# relay_interface.net
KiCad netlist of a schematic drawn in EAGLE
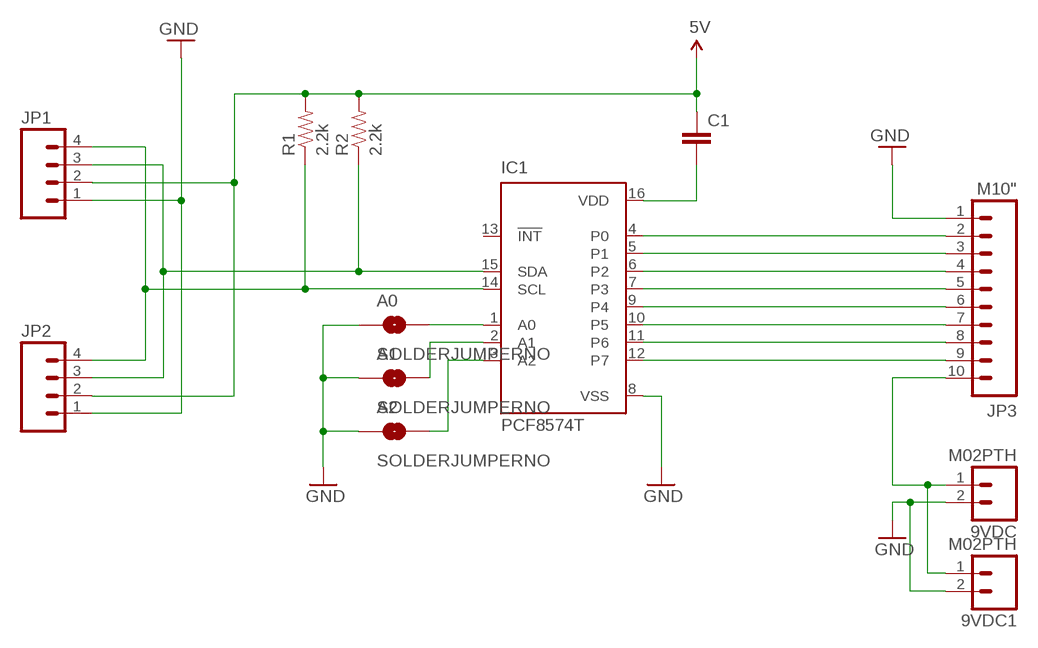
[diagram p0: schematic, sheet 1]

(export (version "E")
  (design (tool "Eeschema 10.0.6"))
  (components
    (comp (ref "9VDC")
      (value "M02PTH")
      (footprint "eagle-import:1X02")
      (libsource (lib "eagle-import") (part "M02PTH"))
    )
    (comp (ref "9VDC1")
      (value "M02PTH")
      (footprint "eagle-import:1X02")
      (libsource (lib "eagle-import") (part "M02PTH"))
    )
    (comp (ref "A0")
      (value "SOLDERJUMPERNO")
      (footprint "eagle-import:SJ_2S-NO")
      (libsource (lib "eagle-import") (part "SOLDERJUMPERNO"))
    )
    (comp (ref "A1")
      (value "SOLDERJUMPERNO")
      (footprint "eagle-import:SJ_2S-NO")
      (libsource (lib "eagle-import") (part "SOLDERJUMPERNO"))
    )
    (comp (ref "A2")
      (value "SOLDERJUMPERNO")
      (footprint "eagle-import:SJ_2S-NO")
      (libsource (lib "eagle-import") (part "SOLDERJUMPERNO"))
    )
    (comp (ref "C1")
      (value "CAPPTH2")
      (footprint "eagle-import:CAP-PTH-SMALL2")
      (libsource (lib "eagle-import") (part "CAPPTH2"))
    )
    (comp (ref "IC1")
      (value "PCF8574T")
      (footprint "eagle-import:SO16W")
      (libsource (lib "eagle-import") (part "PCF8574T"))
    )
    (comp (ref "JP1")
      (value "M04PTH")
      (footprint "eagle-import:1X04")
      (libsource (lib "eagle-import") (part "M04PTH"))
    )
    (comp (ref "JP2")
      (value "M04PTH")
      (footprint "eagle-import:1X04")
      (libsource (lib "eagle-import") (part "M04PTH"))
    )
    (comp (ref "JP3")
      (value "M10\"")
      (footprint "eagle-import:1X10")
      (libsource (lib "eagle-import") (part "M10{dblquote}"))
    )
    (comp (ref "R1")
      (value "2.2k")
      (footprint "eagle-import:AXIAL-0.3")
      (libsource (lib "eagle-import") (part "RESISTORAXIAL-0.3"))
    )
    (comp (ref "R2")
      (value "2.2k")
      (footprint "eagle-import:AXIAL-0.3")
      (libsource (lib "eagle-import") (part "RESISTORAXIAL-0.3"))
    )
  )
  (nets
    (net (code "1") (name "5V") (class "Default")
      (node (ref "C1") (pin "1") (pinfunction "1_1") (pintype "passive"))
      (node (ref "JP1") (pin "2") (pinfunction "2_2") (pintype "passive"))
      (node (ref "JP2") (pin "2") (pinfunction "2_2") (pintype "passive"))
      (node (ref "R1") (pin "P$2") (pinfunction "2_P$2") (pintype "passive"))
      (node (ref "R2") (pin "P$2") (pinfunction "2_P$2") (pintype "passive"))
    )
    (net (code "2") (name "GND") (class "Default")
      (node (ref "9VDC") (pin "2") (pinfunction "2_2") (pintype "passive"))
      (node (ref "9VDC1") (pin "2") (pinfunction "2_2") (pintype "passive"))
      (node (ref "A0") (pin "1") (pinfunction "1_1") (pintype "passive"))
      (node (ref "A1") (pin "1") (pinfunction "1_1") (pintype "passive"))
      (node (ref "A2") (pin "1") (pinfunction "1_1") (pintype "passive"))
      (node (ref "IC1") (pin "8") (pinfunction "VSS_8") (pintype "power_in"))
      (node (ref "JP1") (pin "1") (pinfunction "1_1") (pintype "passive"))
      (node (ref "JP2") (pin "1") (pinfunction "1_1") (pintype "passive"))
      (node (ref "JP3") (pin "1") (pinfunction "1_1") (pintype "passive"))
    )
    (net (code "3") (name "Net-(9VDC-Pad1)") (class "Default")
      (node (ref "9VDC") (pin "1") (pinfunction "1_1") (pintype "passive"))
      (node (ref "9VDC1") (pin "1") (pinfunction "1_1") (pintype "passive"))
      (node (ref "JP3") (pin "10") (pinfunction "10_10") (pintype "passive"))
    )
    (net (code "4") (name "Net-(IC1-A0)") (class "Default")
      (node (ref "A0") (pin "2") (pinfunction "2_2") (pintype "passive"))
      (node (ref "IC1") (pin "1") (pinfunction "A0_1") (pintype "input"))
    )
    (net (code "5") (name "Net-(IC1-A1)") (class "Default")
      (node (ref "A1") (pin "2") (pinfunction "2_2") (pintype "passive"))
      (node (ref "IC1") (pin "2") (pinfunction "A1_2") (pintype "input"))
    )
    (net (code "6") (name "Net-(IC1-A2)") (class "Default")
      (node (ref "A2") (pin "2") (pinfunction "2_2") (pintype "passive"))
      (node (ref "IC1") (pin "3") (pinfunction "A2_3") (pintype "input"))
    )
    (net (code "7") (name "Net-(IC1-P0)") (class "Default")
      (node (ref "IC1") (pin "4") (pinfunction "P0_4") (pintype "bidirectional"))
      (node (ref "JP3") (pin "2") (pinfunction "2_2") (pintype "passive"))
    )
    (net (code "8") (name "Net-(IC1-P1)") (class "Default")
      (node (ref "IC1") (pin "5") (pinfunction "P1_5") (pintype "bidirectional"))
      (node (ref "JP3") (pin "3") (pinfunction "3_3") (pintype "passive"))
    )
    (net (code "9") (name "Net-(IC1-P2)") (class "Default")
      (node (ref "IC1") (pin "6") (pinfunction "P2_6") (pintype "bidirectional"))
      (node (ref "JP3") (pin "4") (pinfunction "4_4") (pintype "passive"))
    )
    (net (code "10") (name "Net-(IC1-P3)") (class "Default")
      (node (ref "IC1") (pin "7") (pinfunction "P3_7") (pintype "bidirectional"))
      (node (ref "JP3") (pin "5") (pinfunction "5_5") (pintype "passive"))
    )
    (net (code "11") (name "Net-(IC1-P4)") (class "Default")
      (node (ref "IC1") (pin "9") (pinfunction "P4_9") (pintype "bidirectional"))
      (node (ref "JP3") (pin "6") (pinfunction "6_6") (pintype "passive"))
    )
    (net (code "12") (name "Net-(IC1-P5)") (class "Default")
      (node (ref "IC1") (pin "10") (pinfunction "P5_10") (pintype "bidirectional"))
      (node (ref "JP3") (pin "7") (pinfunction "7_7") (pintype "passive"))
    )
    (net (code "13") (name "Net-(IC1-P6)") (class "Default")
      (node (ref "IC1") (pin "11") (pinfunction "P6_11") (pintype "bidirectional"))
      (node (ref "JP3") (pin "8") (pinfunction "8_8") (pintype "passive"))
    )
    (net (code "14") (name "Net-(IC1-P7)") (class "Default")
      (node (ref "IC1") (pin "12") (pinfunction "P7_12") (pintype "bidirectional"))
      (node (ref "JP3") (pin "9") (pinfunction "9_9") (pintype "passive"))
    )
    (net (code "15") (name "Net-(IC1-SCL)") (class "Default")
      (node (ref "IC1") (pin "14") (pinfunction "SCL_14") (pintype "input"))
      (node (ref "JP1") (pin "4") (pinfunction "4_4") (pintype "passive"))
      (node (ref "JP2") (pin "4") (pinfunction "4_4") (pintype "passive"))
      (node (ref "R1") (pin "P$1") (pinfunction "1_P$1") (pintype "passive"))
    )
    (net (code "16") (name "Net-(IC1-SDA)") (class "Default")
      (node (ref "IC1") (pin "15") (pinfunction "SDA_15") (pintype "bidirectional"))
      (node (ref "JP1") (pin "3") (pinfunction "3_3") (pintype "passive"))
      (node (ref "JP2") (pin "3") (pinfunction "3_3") (pintype "passive"))
      (node (ref "R2") (pin "P$1") (pinfunction "1_P$1") (pintype "passive"))
    )
    (net (code "17") (name "Net-(IC1-VDD)") (class "Default")
      (node (ref "C1") (pin "2") (pinfunction "2_2") (pintype "passive"))
      (node (ref "IC1") (pin "16") (pinfunction "VDD_16") (pintype "power_in"))
    )
    (net (code "18") (name "unconnected-(IC1-~{INT}-Pad13)") (class "Default")
      (node (ref "IC1") (pin "13") (pinfunction "~{INT}_13") (pintype "output"))
    )
  )
)
